# IV_sensing.net
KiCad netlist of a schematic drawn in Altium Designer
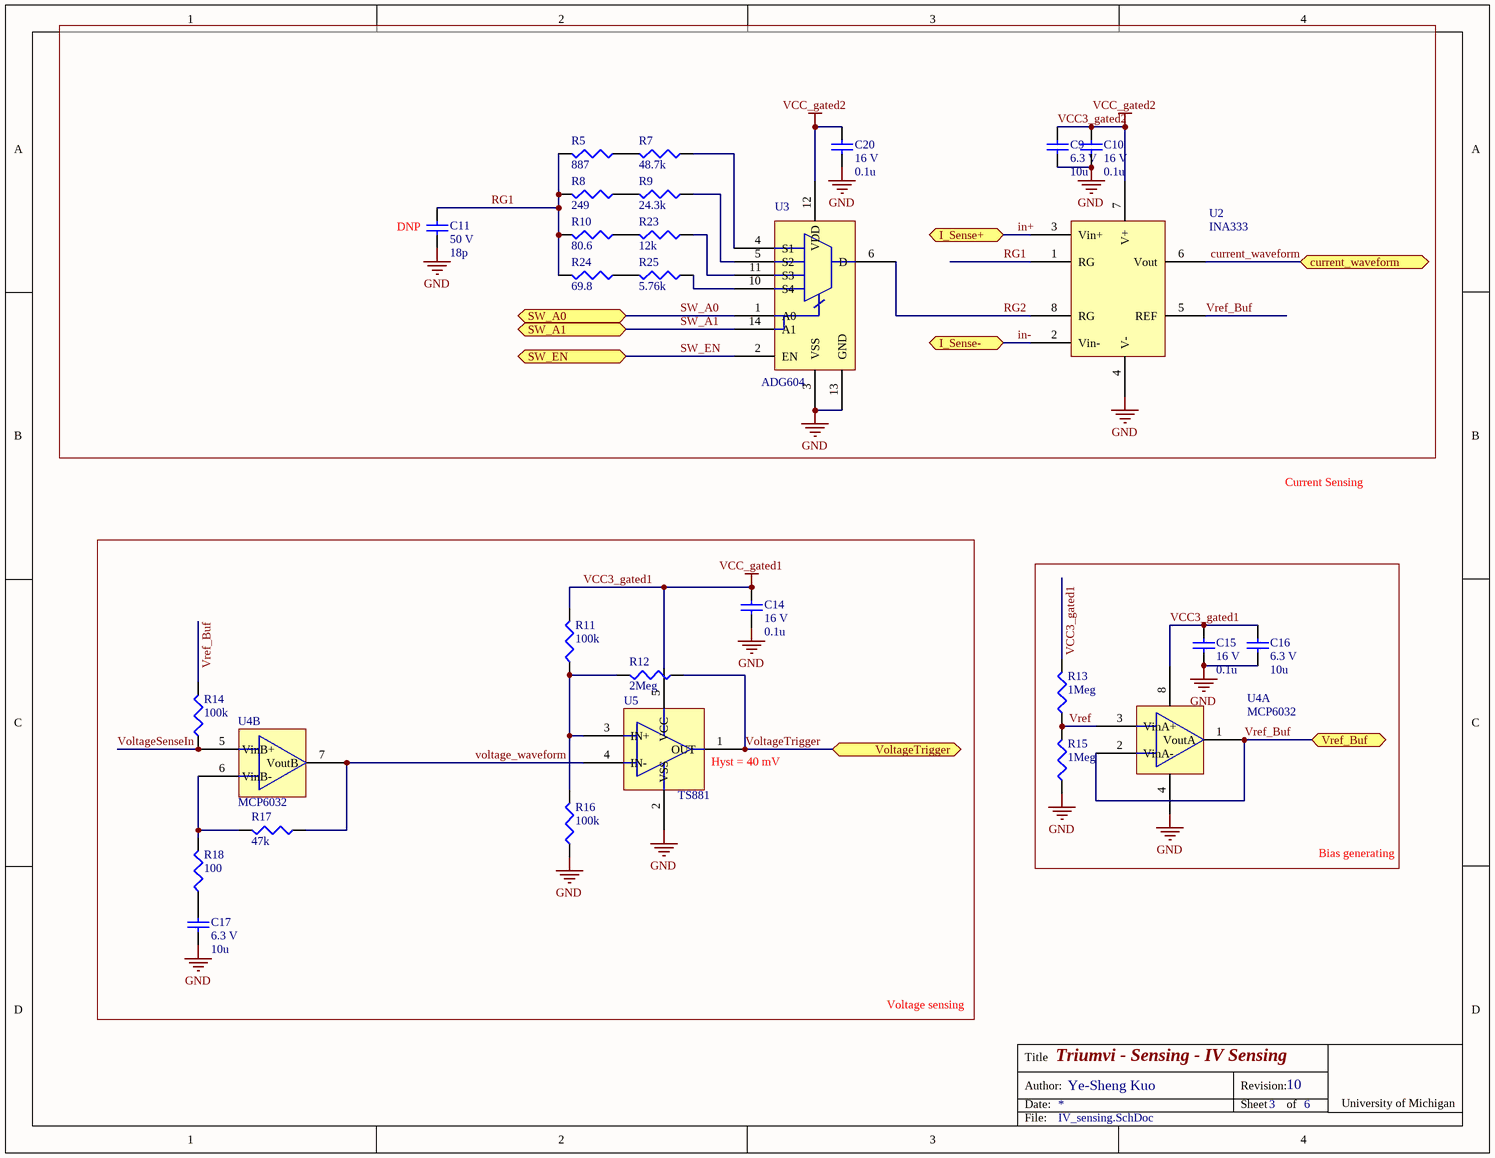
[diagram p0: IV_sensing.SchDoc]

(export (version "E")
  (design (tool "Eeschema 10.0.6"))
  (components
    (comp (ref "C9")
      (value "10u")
      (footprint "0603")
      (description "10µF ±20% 6.3V Ceramic Capacitor X5R 0603")
      (fields
        (field (name "VOLTAGE RATED") "6.3 V")
        (field (name "TOLERANCE") "20%")
        (field (name "MANUFACTURER PART NUMBER") "C1608X5R0J106M080AB")
      )
      (libsource (lib "capacitors") (part "C1608X5R0J106M080AB"))
    )
    (comp (ref "C10")
      (value "0.1u")
      (footprint "0402")
      (description "0.10µF ±10% 16V Ceramic Capacitor X7R 0402")
      (fields
        (field (name "VOLTAGE RATED") "16 V")
        (field (name "TOLERANCE") "10%")
        (field (name "MANUFACTURER PART NUMBER") "GRM155R71C104KA88D")
      )
      (libsource (lib "capacitors") (part "GRM155R71C104KA88D"))
    )
    (comp (ref "C11")
      (value "18p")
      (footprint "0402")
      (description "18pF ±2% 50V Ceramic Capacitor C0G, NP0 0402")
      (fields
        (field (name "TOLERANCE") "2%")
        (field (name "MANUFACTURER PART NUMBER") "500R07S180GV4T")
        (field (name "VOLTAGE RATED") "50 V")
      )
      (libsource (lib "capacitors") (part "500R07S180GV4T"))
    )
    (comp (ref "C14")
      (value "0.1u")
      (footprint "0402")
      (description "0.10µF ±10% 16V Ceramic Capacitor X7R 0402")
      (fields
        (field (name "VOLTAGE RATED") "16 V")
        (field (name "TOLERANCE") "10%")
        (field (name "MANUFACTURER PART NUMBER") "GRM155R71C104KA88D")
      )
      (libsource (lib "capacitors") (part "GRM155R71C104KA88D"))
    )
    (comp (ref "C15")
      (value "0.1u")
      (footprint "0402")
      (description "0.10µF ±10% 16V Ceramic Capacitor X7R 0402")
      (fields
        (field (name "VOLTAGE RATED") "16 V")
        (field (name "TOLERANCE") "10%")
        (field (name "MANUFACTURER PART NUMBER") "GRM155R71C104KA88D")
      )
      (libsource (lib "capacitors") (part "GRM155R71C104KA88D"))
    )
    (comp (ref "C16")
      (value "10u")
      (footprint "0603")
      (description "10µF ±20% 6.3V Ceramic Capacitor X5R 0603")
      (fields
        (field (name "VOLTAGE RATED") "6.3 V")
        (field (name "TOLERANCE") "20%")
        (field (name "MANUFACTURER PART NUMBER") "C1608X5R0J106M080AB")
      )
      (libsource (lib "capacitors") (part "C1608X5R0J106M080AB"))
    )
    (comp (ref "C17")
      (value "10u")
      (footprint "0603")
      (description "10µF ±20% 6.3V Ceramic Capacitor X5R 0603")
      (fields
        (field (name "VOLTAGE RATED") "6.3 V")
        (field (name "TOLERANCE") "20%")
        (field (name "MANUFACTURER PART NUMBER") "C1608X5R0J106M080AB")
      )
      (libsource (lib "capacitors") (part "C1608X5R0J106M080AB"))
    )
    (comp (ref "C20")
      (value "0.1u")
      (footprint "0402")
      (description "0.10µF ±10% 16V Ceramic Capacitor X7R 0402")
      (fields
        (field (name "VOLTAGE RATED") "16 V")
        (field (name "TOLERANCE") "10%")
        (field (name "MANUFACTURER PART NUMBER") "GRM155R71C104KA88D")
      )
      (libsource (lib "capacitors") (part "GRM155R71C104KA88D"))
    )
    (comp (ref "R5")
      (value "887")
      (footprint "0402")
      (description "RES SMD 887 OHM 1% 1/16W 0402")
      (fields
        (field (name "MANUFACTURER PART NUMBER") "CRCW0402887RFKED")
        (field (name "MANUFACTURER") "Vishay Dale")
      )
      (libsource (lib "resistors") (part "CRCW0402887RFKED"))
    )
    (comp (ref "R7")
      (value "48.7k")
      (footprint "0402")
      (description "RES SMD 48.7K OHM 0.5% 1/16W 0402")
      (fields
        (field (name "MANUFACTURER PART NUMBER") "RT0402DRD0748K7L")
        (field (name "MANUFACTURER") "Yageo")
      )
      (libsource (lib "resistors") (part "RT0402DRD0748K7L"))
    )
    (comp (ref "R8")
      (value "249")
      (footprint "0402")
      (description "RES SMD 249 OHM 1% 1/16W 0402")
      (fields
        (field (name "MANUFACTURER PART NUMBER") "CRCW0402249RFKED")
        (field (name "MANUFACTURER") "Vishay Dale")
      )
      (libsource (lib "resistors") (part "CRCW0402249RFKED"))
    )
    (comp (ref "R9")
      (value "24.3k")
      (footprint "0402")
      (description "RES SMD 24.3K OHM 0.5% 1/16W 0402")
      (fields
        (field (name "MANUFACTURER PART NUMBER") "RC0402FR-0724K3L")
        (field (name "MANUFACTURER") "Yageo")
      )
      (libsource (lib "resistors") (part "RC0402FR-0724K3L"))
    )
    (comp (ref "R10")
      (value "80.6")
      (footprint "0402")
      (description "RES SMD 80.6 OHM 1% 1/16W 0402")
      (fields
        (field (name "MANUFACTURER PART NUMBER") "CRCW040280R6FKED")
        (field (name "MANUFACTURER") "Vishay Dale")
      )
      (libsource (lib "resistors") (part "CRCW040280R6FKED"))
    )
    (comp (ref "R11")
      (value "100k")
      (footprint "0402")
      (description "RES SMD 100K OHM 1% 1/16W 0402")
      (fields (field (name "TOLERANCE") "1%") (field (name "POWER") "1/16 W"))
      (libsource (lib "resistors") (part "CRCW0402100KFKED"))
    )
    (comp (ref "R12")
      (value "2Meg")
      (footprint "0402")
      (description "RES SMD 2M OHM 1% 1/16W 0402")
      (fields (field (name "TOLERANCE") "1%") (field (name "POWER") "1/16 W"))
      (libsource (lib "resistors") (part "CRCW04022M00FKED"))
    )
    (comp (ref "R13")
      (value "1Meg")
      (footprint "0402")
      (description "RES SMD 1M OHM 1% 1/16W 0402")
      (fields (field (name "TOLERANCE") "1%") (field (name "POWER") "1/16 W"))
      (libsource (lib "resistors") (part "CRCW04021M00FKED"))
    )
    (comp (ref "R14")
      (value "100k")
      (footprint "0402")
      (description "RES SMD 100K OHM 1% 1/16W 0402")
      (fields (field (name "TOLERANCE") "1%") (field (name "POWER") "1/16 W"))
      (libsource (lib "resistors") (part "CRCW0402100KFKED"))
    )
    (comp (ref "R15")
      (value "1Meg")
      (footprint "0402")
      (description "RES SMD 1M OHM 1% 1/16W 0402")
      (fields (field (name "TOLERANCE") "1%") (field (name "POWER") "1/16 W"))
      (libsource (lib "resistors") (part "CRCW04021M00FKED"))
    )
    (comp (ref "R16")
      (value "100k")
      (footprint "0402")
      (description "RES SMD 100K OHM 1% 1/16W 0402")
      (fields (field (name "TOLERANCE") "1%") (field (name "POWER") "1/16 W"))
      (libsource (lib "resistors") (part "CRCW0402100KFKED"))
    )
    (comp (ref "R17")
      (value "47k")
      (footprint "0402")
      (description "RES SMD 47K OHM 1% 1/16W 0402")
      (fields (field (name "TOLERANCE") "1%") (field (name "POWER") "1/16 W"))
      (libsource (lib "resistors") (part "CRCW040247K0FKED"))
    )
    (comp (ref "R18")
      (value "100")
      (footprint "0402")
      (description "RES SMD 100 OHM 1% 1/16W 0402")
      (fields (field (name "TOLERANCE") "1%") (field (name "POWER") "1/16 W"))
      (libsource (lib "resistors") (part "CRCW0402100RFKED"))
    )
    (comp (ref "R23")
      (value "12k")
      (footprint "0402")
      (description "RES SMD 12K OHM 0.5% 1/16W 0402")
      (fields
        (field (name "MANUFACTURER PART NUMBER") "RT0402DRD0712KL")
        (field (name "MANUFACTURER") "Yageo")
      )
      (libsource (lib "resistors") (part "RT0402DRD0712KL"))
    )
    (comp (ref "R24")
      (value "69.8")
      (footprint "0402")
      (description "RES SMD 69.8 OHM 1% 1/16W 0402")
      (fields
        (field (name "MANUFACTURER PART NUMBER") "CRCW040269R8FKED")
        (field (name "MANUFACTURER") "Vishay Dale")
      )
      (libsource (lib "resistors") (part "CRCW040269R8FKED"))
    )
    (comp (ref "R25")
      (value "5.76k")
      (footprint "0402")
      (description "RES SMD 5.76K OHM 0.5% 1/16W 0402")
      (fields
        (field (name "MANUFACTURER PART NUMBER") "RC0402FR-075K76L")
        (field (name "MANUFACTURER") "Yageo")
      )
      (libsource (lib "resistors") (part "RC0402FR-075K76L"))
    )
    (comp (ref "U2")
      (value "INA333")
      (footprint "MSOP-8")
      (description "Micro-Power (50uA), Zero-Drift, Rail-to-Rail Out  Instrumentation Amplifier")
      (libsource (lib "amplifier") (part "INA333"))
    )
    (comp (ref "U3")
      (value "ADG604")
      (footprint "TSSOP-14")
      (description "1 pC Charge Injection, 100 pA Leakage  CMOS  5 V/5 V/3 V 4-Channel Multiplexer")
      (libsource (lib "multiplexer") (part "ADG604"))
    )
    (comp (ref "U4")
      (value "MCP6032")
      (footprint "MSOP-8")
      (description "0.9 µA, High Precision Op Amps")
      (libsource (lib "amplifier") (part "MCP6032"))
    )
    (comp (ref "U5")
      (value "TS881")
      (footprint "SC70-5")
      (description "Rail-to-rail 0.9 V nanopower comparator")
      (libsource (lib "comparators") (part "TS881"))
    )
  )
  (nets
    (net (code "1") (name "/RG1") (class "Default")
      (node (ref "C11") (pin "1") (pintype "passive"))
      (node (ref "R10") (pin "1") (pintype "passive"))
      (node (ref "R24") (pin "1") (pintype "passive"))
      (node (ref "R5") (pin "1") (pintype "passive"))
      (node (ref "R8") (pin "1") (pintype "passive"))
      (node (ref "U2") (pin "1") (pinfunction "RG_1") (pintype "passive"))
    )
    (net (code "2") (name "/RG2") (class "Default")
      (node (ref "U2") (pin "8") (pinfunction "RG_8") (pintype "passive"))
      (node (ref "U3") (pin "6") (pinfunction "D_6") (pintype "passive"))
    )
    (net (code "3") (name "/SW_A0") (class "Default")
      (node (ref "U3") (pin "1") (pinfunction "A0_1") (pintype "passive"))
    )
    (net (code "4") (name "/SW_A1") (class "Default")
      (node (ref "U3") (pin "14") (pinfunction "A1_14") (pintype "passive"))
    )
    (net (code "5") (name "/SW_EN") (class "Default")
      (node (ref "U3") (pin "2") (pinfunction "EN_2") (pintype "passive"))
    )
    (net (code "6") (name "/VoltageSenseIn") (class "Default")
      (node (ref "R14") (pin "2") (pintype "passive"))
      (node (ref "U4") (pin "5") (pinfunction "VinB+_5") (pintype "passive"))
    )
    (net (code "7") (name "/VoltageTrigger") (class "Default")
      (node (ref "R12") (pin "2") (pintype "passive"))
      (node (ref "U5") (pin "1") (pinfunction "OUT_1") (pintype "passive"))
    )
    (net (code "8") (name "/Vref") (class "Default")
      (node (ref "R13") (pin "2") (pintype "passive"))
      (node (ref "R15") (pin "1") (pintype "passive"))
      (node (ref "U4") (pin "3") (pinfunction "VinA+_3") (pintype "passive"))
    )
    (net (code "9") (name "/Vref_Buf") (class "Default")
      (node (ref "R14") (pin "1") (pintype "passive"))
      (node (ref "U2") (pin "5") (pinfunction "REF_5") (pintype "passive"))
      (node (ref "U4") (pin "1") (pinfunction "VoutA_1") (pintype "passive"))
      (node (ref "U4") (pin "2") (pinfunction "VinA-_2") (pintype "passive"))
    )
    (net (code "10") (name "/current_waveform") (class "Default")
      (node (ref "U2") (pin "6") (pinfunction "Vout_6") (pintype "passive"))
    )
    (net (code "11") (name "/in+") (class "Default")
      (node (ref "U2") (pin "3") (pinfunction "Vin+_3") (pintype "passive"))
    )
    (net (code "12") (name "/in-") (class "Default")
      (node (ref "U2") (pin "2") (pinfunction "Vin-_2") (pintype "passive"))
    )
    (net (code "13") (name "/voltage_waveform") (class "Default")
      (node (ref "R17") (pin "2") (pintype "passive"))
      (node (ref "U4") (pin "7") (pinfunction "VoutB_7") (pintype "passive"))
      (node (ref "U5") (pin "4") (pinfunction "IN-_4") (pintype "passive"))
    )
    (net (code "14") (name "GND") (class "Default")
      (node (ref "C10") (pin "2") (pintype "passive"))
      (node (ref "C11") (pin "2") (pintype "passive"))
      (node (ref "C14") (pin "2") (pintype "passive"))
      (node (ref "C15") (pin "2") (pintype "passive"))
      (node (ref "C16") (pin "2") (pintype "passive"))
      (node (ref "C17") (pin "2") (pintype "passive"))
      (node (ref "C20") (pin "2") (pintype "passive"))
      (node (ref "C9") (pin "2") (pintype "passive"))
      (node (ref "R15") (pin "2") (pintype "passive"))
      (node (ref "R16") (pin "2") (pintype "passive"))
      (node (ref "U2") (pin "4") (pinfunction "V-_4") (pintype "passive"))
      (node (ref "U3") (pin "13") (pinfunction "GND_13") (pintype "passive"))
      (node (ref "U3") (pin "3") (pinfunction "VSS_3") (pintype "passive"))
      (node (ref "U4") (pin "4") (pinfunction "VSS_4") (pintype "passive"))
      (node (ref "U5") (pin "2") (pinfunction "VSS_2") (pintype "passive"))
    )
    (net (code "15") (name "Net-(C17-Pad1)") (class "Default")
      (node (ref "C17") (pin "1") (pintype "passive"))
      (node (ref "R18") (pin "2") (pintype "passive"))
    )
    (net (code "16") (name "Net-(R5-Pad2)") (class "Default")
      (node (ref "R5") (pin "2") (pintype "passive"))
      (node (ref "R7") (pin "1") (pintype "passive"))
    )
    (net (code "17") (name "Net-(R8-Pad2)") (class "Default")
      (node (ref "R8") (pin "2") (pintype "passive"))
      (node (ref "R9") (pin "1") (pintype "passive"))
    )
    (net (code "18") (name "Net-(R10-Pad2)") (class "Default")
      (node (ref "R10") (pin "2") (pintype "passive"))
      (node (ref "R23") (pin "1") (pintype "passive"))
    )
    (net (code "19") (name "Net-(R24-Pad2)") (class "Default")
      (node (ref "R24") (pin "2") (pintype "passive"))
      (node (ref "R25") (pin "1") (pintype "passive"))
    )
    (net (code "20") (name "Net-(U3-S1)") (class "Default")
      (node (ref "R7") (pin "2") (pintype "passive"))
      (node (ref "U3") (pin "4") (pinfunction "S1_4") (pintype "passive"))
    )
    (net (code "21") (name "Net-(U3-S2)") (class "Default")
      (node (ref "R9") (pin "2") (pintype "passive"))
      (node (ref "U3") (pin "5") (pinfunction "S2_5") (pintype "passive"))
    )
    (net (code "22") (name "Net-(U3-S3)") (class "Default")
      (node (ref "R23") (pin "2") (pintype "passive"))
      (node (ref "U3") (pin "11") (pinfunction "S3_11") (pintype "passive"))
    )
    (net (code "23") (name "Net-(U3-S4)") (class "Default")
      (node (ref "R25") (pin "2") (pintype "passive"))
      (node (ref "U3") (pin "10") (pinfunction "S4_10") (pintype "passive"))
    )
    (net (code "24") (name "Net-(U4B-VinB-)") (class "Default")
      (node (ref "R17") (pin "1") (pintype "passive"))
      (node (ref "R18") (pin "1") (pintype "passive"))
      (node (ref "U4") (pin "6") (pinfunction "VinB-_6") (pintype "passive"))
    )
    (net (code "25") (name "Net-(U5-IN+)") (class "Default")
      (node (ref "R11") (pin "2") (pintype "passive"))
      (node (ref "R12") (pin "1") (pintype "passive"))
      (node (ref "R16") (pin "1") (pintype "passive"))
      (node (ref "U5") (pin "3") (pinfunction "IN+_3") (pintype "passive"))
    )
    (net (code "26") (name "VCC_gated1") (class "Default")
      (node (ref "C14") (pin "1") (pintype "passive"))
      (node (ref "C15") (pin "1") (pintype "passive"))
      (node (ref "C16") (pin "1") (pintype "passive"))
      (node (ref "R11") (pin "1") (pintype "passive"))
      (node (ref "R13") (pin "1") (pintype "passive"))
      (node (ref "U4") (pin "8") (pinfunction "VDD_8") (pintype "passive"))
      (node (ref "U5") (pin "5") (pinfunction "VCC_5") (pintype "passive"))
    )
    (net (code "27") (name "VCC_gated2") (class "Default")
      (node (ref "C10") (pin "1") (pintype "passive"))
      (node (ref "C20") (pin "1") (pintype "passive"))
      (node (ref "C9") (pin "1") (pintype "passive"))
      (node (ref "U2") (pin "7") (pinfunction "V+_7") (pintype "passive"))
      (node (ref "U3") (pin "12") (pinfunction "VDD_12") (pintype "passive"))
    )
  )
)
